# YOTSUBA_GNSS-receiver_MAX_ver_1_4.net
KiCad netlist of a schematic drawn in EAGLE
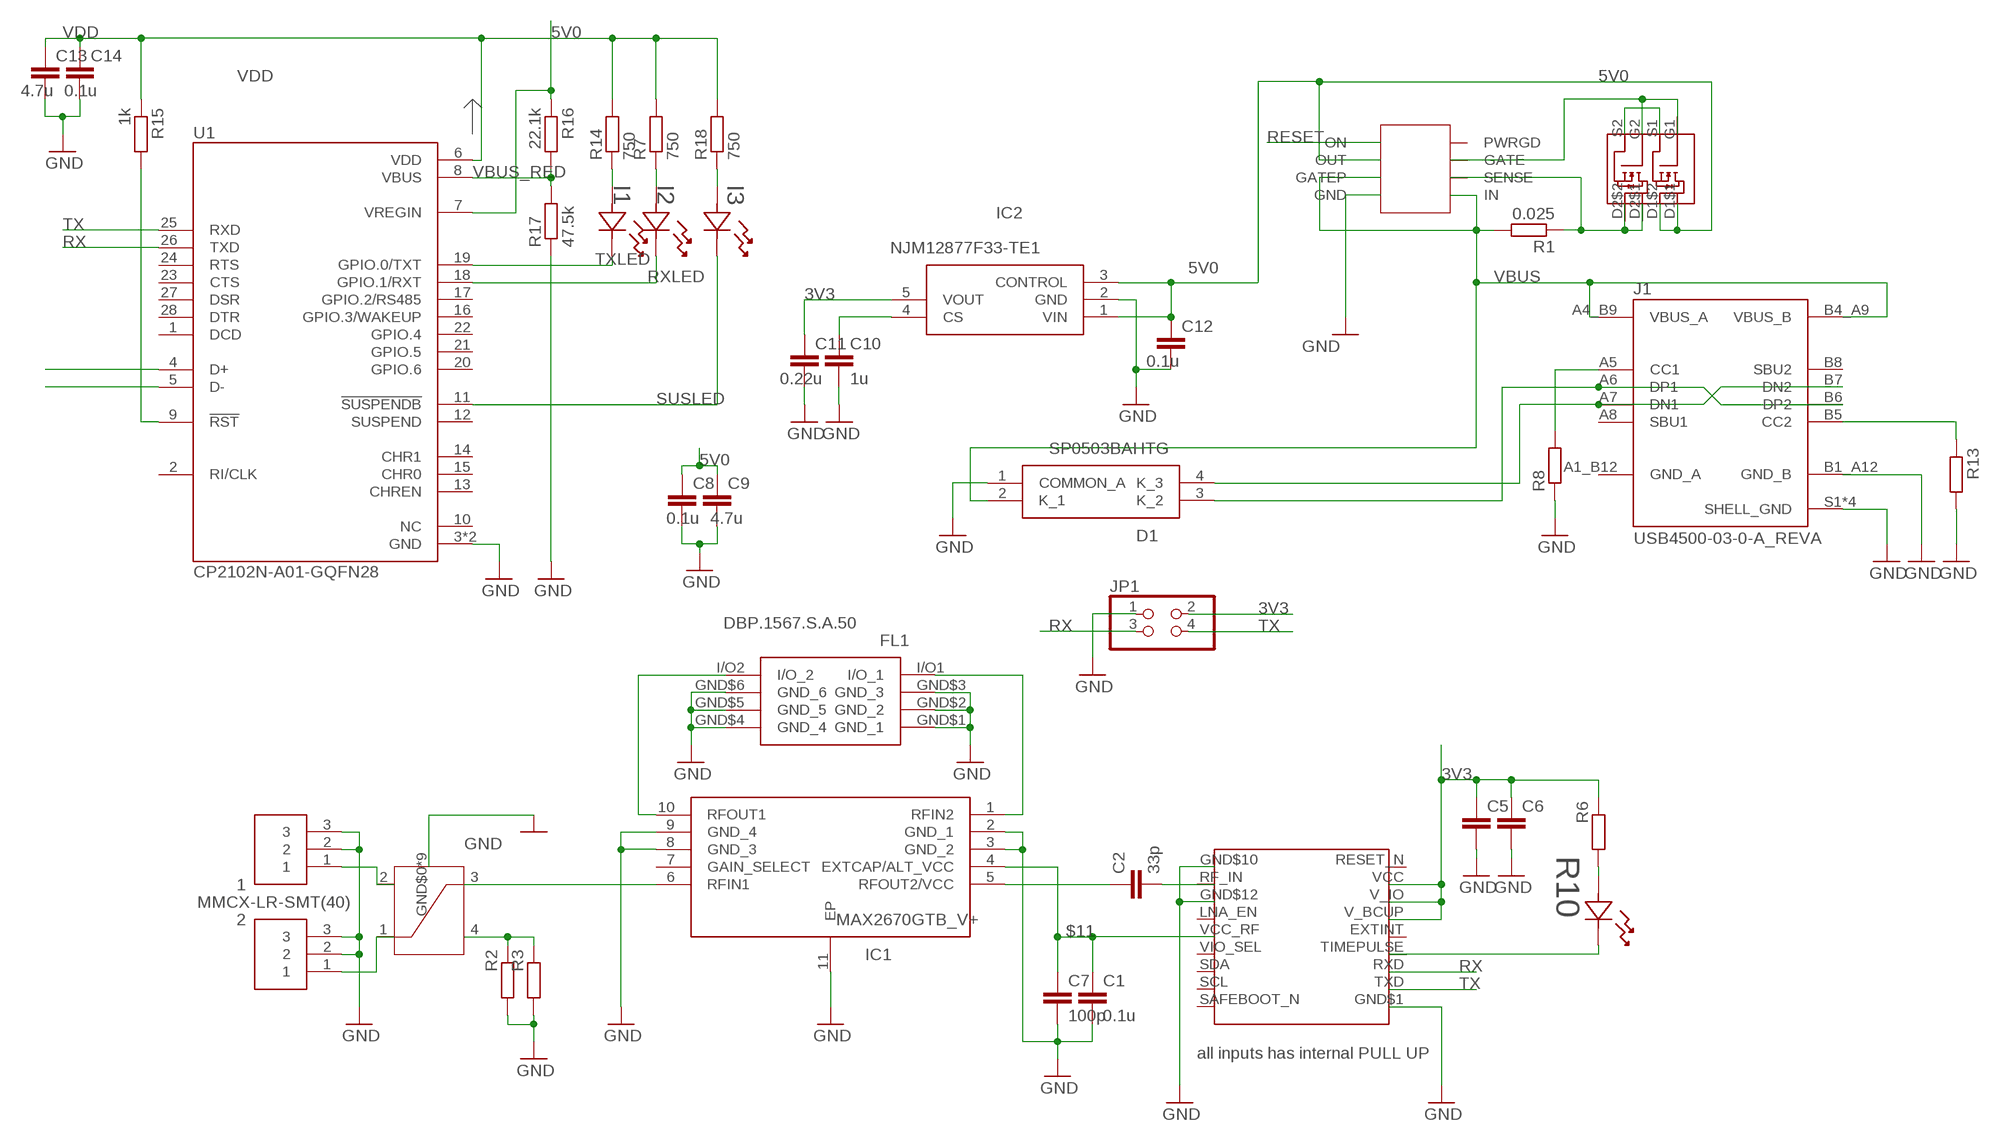
[diagram p0: schematic, sheet 1]

(export (version "E")
  (design (tool "Eeschema 10.0.6"))
  (components
    (comp (ref "1")
      (value "MMCX-LR-SMT(40)")
      (footprint "eagle-import:MMCX-LR-SMT(40)")
      (libsource (lib "eagle-import") (part "MMCX-LR-SMT(40)"))
    )
    (comp (ref "2")
      (value "MMCX-LR-SMT(40)")
      (footprint "eagle-import:MMCX-LR-SMT(40)")
      (libsource (lib "eagle-import") (part "MMCX-LR-SMT(40)"))
    )
    (comp (ref "C1")
      (value "0.1u")
      (footprint "eagle-import:C1608")
      (libsource (lib "eagle-import") (part "C-EUC1608"))
    )
    (comp (ref "C2")
      (value "33p")
      (footprint "eagle-import:C1608")
      (libsource (lib "eagle-import") (part "C-EUC1608"))
    )
    (comp (ref "C5")
      (value "C-EUC1608")
      (footprint "eagle-import:C1608")
      (libsource (lib "eagle-import") (part "C-EUC1608"))
    )
    (comp (ref "C6")
      (value "C-EUC1608")
      (footprint "eagle-import:C1608")
      (libsource (lib "eagle-import") (part "C-EUC1608"))
    )
    (comp (ref "C7")
      (value "100p")
      (footprint "eagle-import:C1608")
      (libsource (lib "eagle-import") (part "C-EUC1608"))
    )
    (comp (ref "C8")
      (value "0.1u")
      (footprint "eagle-import:C1608")
      (libsource (lib "eagle-import") (part "C-EUC1608"))
    )
    (comp (ref "C9")
      (value "4.7u")
      (footprint "eagle-import:C1608")
      (libsource (lib "eagle-import") (part "C-EUC1608"))
    )
    (comp (ref "C10")
      (value "1u")
      (footprint "eagle-import:C1608")
      (libsource (lib "eagle-import") (part "C-EUC1608"))
    )
    (comp (ref "C11")
      (value "0.22u")
      (footprint "eagle-import:C1608")
      (libsource (lib "eagle-import") (part "C-EUC1608"))
    )
    (comp (ref "C12")
      (value "0.1u")
      (footprint "eagle-import:C1608")
      (libsource (lib "eagle-import") (part "C-EUC1608"))
    )
    (comp (ref "C13")
      (value "4.7u")
      (footprint "eagle-import:C1608")
      (libsource (lib "eagle-import") (part "C-EUC1608"))
    )
    (comp (ref "C14")
      (value "0.1u")
      (footprint "eagle-import:C1608")
      (libsource (lib "eagle-import") (part "C-EUC1608"))
    )
    (comp (ref "D1")
      (value "SP0503BAHTG")
      (footprint "eagle-import:SP0503BAHTG")
      (fields (field (name "MOUSER_PART_NUMBER") "576-SP0503BAHTG"))
      (libsource (lib "eagle-import") (part "SP0503BAHTG"))
    )
    (comp (ref "FL1")
      (value "DBP.1567.S.A.50")
      (footprint "eagle-import:DBP1567SA50")
      (libsource (lib "eagle-import") (part "DBP.1567.S.A.50"))
    )
    (comp (ref "I1")
      (value "SML-E12P8WT86")
      (footprint "eagle-import:LED_SMLD12_ROM")
      (fields (field (name "COPYRIGHT") "Copyright (C) 2023 Ultra Librarian. All rights reserved."))
      (libsource (lib "eagle-import") (part "SML-E12P8WT86"))
    )
    (comp (ref "I2")
      (value "SML-E12P8WT86")
      (footprint "eagle-import:LED_SMLD12_ROM")
      (fields (field (name "COPYRIGHT") "Copyright (C) 2023 Ultra Librarian. All rights reserved."))
      (libsource (lib "eagle-import") (part "SML-E12P8WT86"))
    )
    (comp (ref "I3")
      (value "SML-E12P8WT86")
      (footprint "eagle-import:LED_SMLD12_ROM")
      (fields (field (name "COPYRIGHT") "Copyright (C) 2023 Ultra Librarian. All rights reserved."))
      (libsource (lib "eagle-import") (part "SML-E12P8WT86"))
    )
    (comp (ref "IC1")
      (value "MAX2670GTB_V+")
      (footprint "eagle-import:SON50P300X300X80-11N")
      (fields
        (field (name "MANUFACTURER_PART_NUMBER") "MAX2670GTB/V+")
        (field (name "MOUSER_PART_NUMBER") "700-MAX2670GTB/V+")
      )
      (libsource (lib "eagle-import") (part "MAX2670GTB_V+"))
    )
    (comp (ref "IC2")
      (value "NJM12877F33-TE1")
      (footprint "eagle-import:SOT95P280X120-5N")
      (fields (field (name "MOUSER_PART_NUMBER") "513-NJM12877F33-TE1"))
      (libsource (lib "eagle-import") (part "NJM12877F33-TE1"))
    )
    (comp (ref "J1")
      (value "USB4500-03-0-A_REVA")
      (footprint "eagle-import:GCT_USB4500-03-0-A_REVA")
      (fields
        (field (name "DIGI-KEY_PART_NUMBER") "2073-USB4500-03-0-ATR-ND")
        (field (name "MF") "Global Connector Technology")
        (field (name "MP") "USB4500-03-0-A")
      )
      (libsource (lib "eagle-import") (part "USB4500-03-0-A_REVA"))
    )
    (comp (ref "JP1")
      (value "PINHD-2X2")
      (footprint "eagle-import:2X02")
      (libsource (lib "eagle-import") (part "PINHD-2X2"))
    )
    (comp (ref "R1")
      (value "0.025")
      (footprint "eagle-import:R0603")
      (libsource (lib "eagle-import") (part "R-EU_R0603"))
    )
    (comp (ref "R2")
      (value "R-EU_R0603")
      (footprint "eagle-import:R0603")
      (libsource (lib "eagle-import") (part "R-EU_R0603"))
    )
    (comp (ref "R3")
      (value "R-EU_R0603")
      (footprint "eagle-import:R0603")
      (libsource (lib "eagle-import") (part "R-EU_R0603"))
    )
    (comp (ref "R6")
      (value "R-EU_R0603")
      (footprint "eagle-import:R0603")
      (libsource (lib "eagle-import") (part "R-EU_R0603"))
    )
    (comp (ref "R7")
      (value "750")
      (footprint "eagle-import:R0603")
      (libsource (lib "eagle-import") (part "R-EU_R0603"))
    )
    (comp (ref "R8")
      (value "R-EU_R0603")
      (footprint "eagle-import:R0603")
      (libsource (lib "eagle-import") (part "R-EU_R0603"))
    )
    (comp (ref "R10")
      (value "SML-E12P8WT86")
      (footprint "eagle-import:LED_SMLD12_ROM")
      (fields (field (name "COPYRIGHT") "Copyright (C) 2023 Ultra Librarian. All rights reserved."))
      (libsource (lib "eagle-import") (part "SML-E12P8WT86"))
    )
    (comp (ref "R13")
      (value "R-EU_R0603")
      (footprint "eagle-import:R0603")
      (libsource (lib "eagle-import") (part "R-EU_R0603"))
    )
    (comp (ref "R14")
      (value "750")
      (footprint "eagle-import:R0603")
      (libsource (lib "eagle-import") (part "R-EU_R0603"))
    )
    (comp (ref "R15")
      (value "1k")
      (footprint "eagle-import:R0603")
      (libsource (lib "eagle-import") (part "R-EU_R0603"))
    )
    (comp (ref "R16")
      (value "22.1k")
      (footprint "eagle-import:R0603")
      (libsource (lib "eagle-import") (part "R-EU_R0603"))
    )
    (comp (ref "R17")
      (value "47.5k")
      (footprint "eagle-import:R0603")
      (libsource (lib "eagle-import") (part "R-EU_R0603"))
    )
    (comp (ref "R18")
      (value "750")
      (footprint "eagle-import:R0603")
      (libsource (lib "eagle-import") (part "R-EU_R0603"))
    )
    (comp (ref "U$1")
      (value "MAX_M10S")
      (footprint "eagle-import:MAX-M10S")
      (libsource (lib "eagle-import") (part "MAX_M10S"))
    )
    (comp (ref "U$3")
      (value "HC125.A")
      (footprint "eagle-import:HC125.A")
      (libsource (lib "eagle-import") (part "HC125.A"))
    )
    (comp (ref "U$7")
      (value "DMG6898LSD")
      (footprint "eagle-import:SOIC127P600X150-8N")
      (libsource (lib "eagle-import") (part "DMG6898LSD"))
    )
    (comp (ref "U$8")
      (value "LTC4361")
      (footprint "eagle-import:SOP65P280X100-8N")
      (libsource (lib "eagle-import") (part "LTC4361"))
    )
    (comp (ref "U1")
      (value "CP2102N-A01-GQFN28")
      (footprint "eagle-import:QFN50P500X500X80-29N")
      (fields (field (name "MF") "Silicon Labs"))
      (libsource (lib "eagle-import") (part "CP2102N-A01-GQFN28"))
    )
  )
  (nets
    (net (code "1") (name "/$11") (class "Default")
      (node (ref "C1") (pin "1") (pinfunction "1_1") (pintype "passive"))
      (node (ref "C7") (pin "1") (pinfunction "1_1") (pintype "passive"))
      (node (ref "IC1") (pin "4") (pinfunction "EXTCAP/ALT_VCC_4") (pintype "bidirectional"))
      (node (ref "U$1") (pin "VCC_RF") (pinfunction "VCC_RF_VCC_RF") (pintype "bidirectional"))
    )
    (net (code "2") (name "/3V3") (class "Default")
      (node (ref "C11") (pin "1") (pinfunction "1_1") (pintype "passive"))
      (node (ref "C5") (pin "1") (pinfunction "1_1") (pintype "passive"))
      (node (ref "C6") (pin "1") (pinfunction "1_1") (pintype "passive"))
      (node (ref "IC2") (pin "5") (pinfunction "VOUT_5") (pintype "bidirectional"))
      (node (ref "JP1") (pin "2") (pinfunction "2_2") (pintype "passive"))
      (node (ref "R6") (pin "2") (pinfunction "2_2") (pintype "passive"))
      (node (ref "U$1") (pin "VCC") (pinfunction "VCC_VCC") (pintype "bidirectional"))
      (node (ref "U$1") (pin "V_BCUP") (pinfunction "V_BCKP_V_BCUP") (pintype "bidirectional"))
      (node (ref "U$1") (pin "V_IO") (pinfunction "V_IO_V_IO") (pintype "bidirectional"))
    )
    (net (code "3") (name "/5V0") (class "Default")
      (node (ref "C12") (pin "1") (pinfunction "1_1") (pintype "passive"))
      (node (ref "C8") (pin "1") (pinfunction "1_1") (pintype "passive"))
      (node (ref "C9") (pin "1") (pinfunction "1_1") (pintype "passive"))
      (node (ref "IC2") (pin "1") (pinfunction "VIN_1") (pintype "bidirectional"))
      (node (ref "IC2") (pin "3") (pinfunction "CONTROL_3") (pintype "bidirectional"))
      (node (ref "R16") (pin "1") (pinfunction "1_1") (pintype "passive"))
      (node (ref "U$7") (pin "D1$1") (pinfunction "D1$1_D1$1") (pintype "bidirectional"))
      (node (ref "U$7") (pin "D1$2") (pinfunction "D1$2_D1$2") (pintype "bidirectional"))
      (node (ref "U$8") (pin "OUT") (pinfunction "OUT_OUT") (pintype "bidirectional"))
      (node (ref "U1") (pin "7") (pinfunction "VREGIN_7") (pintype "power_in"))
    )
    (net (code "4") (name "/D+") (class "Default")
      (node (ref "D1") (pin "3") (pinfunction "K_2_3") (pintype "bidirectional"))
      (node (ref "J1") (pin "A6") (pinfunction "DP1_A6") (pintype "bidirectional"))
      (node (ref "J1") (pin "B6") (pinfunction "DP2_B6") (pintype "bidirectional"))
      (node (ref "U1") (pin "4") (pinfunction "D+_4") (pintype "bidirectional"))
    )
    (net (code "5") (name "/D-") (class "Default")
      (node (ref "D1") (pin "4") (pinfunction "K_3_4") (pintype "bidirectional"))
      (node (ref "J1") (pin "A7") (pinfunction "DN1_A7") (pintype "bidirectional"))
      (node (ref "J1") (pin "B7") (pinfunction "DN2_B7") (pintype "bidirectional"))
      (node (ref "U1") (pin "5") (pinfunction "D-_5") (pintype "bidirectional"))
    )
    (net (code "6") (name "/GND_A") (class "Default")
      (node (ref "J1") (pin "A1_B12") (pinfunction "GND_A_A1_B12") (pintype "power_in"))
    )
    (net (code "7") (name "/RESET") (class "Default")
      (node (ref "U$8") (pin "ON") (pinfunction "ON_ON") (pintype "bidirectional"))
    )
    (net (code "8") (name "/RX") (class "Default")
      (node (ref "JP1") (pin "3") (pinfunction "3_3") (pintype "passive"))
      (node (ref "U$1") (pin "RXD") (pinfunction "RXD_RXD") (pintype "bidirectional"))
      (node (ref "U1") (pin "26") (pinfunction "TXD_26") (pintype "output"))
    )
    (net (code "9") (name "/RXLED") (class "Default")
      (node (ref "I2") (pin "1") (pinfunction "1_1") (pintype "passive"))
      (node (ref "U1") (pin "18") (pinfunction "GPIO.1/RXT_18") (pintype "bidirectional"))
    )
    (net (code "10") (name "/SUSLED") (class "Default")
      (node (ref "I3") (pin "1") (pinfunction "1_1") (pintype "passive"))
      (node (ref "U1") (pin "11") (pinfunction "~{SUSPENDB}_11") (pintype "output"))
    )
    (net (code "11") (name "/TX") (class "Default")
      (node (ref "JP1") (pin "4") (pinfunction "4_4") (pintype "passive"))
      (node (ref "U$1") (pin "TXD") (pinfunction "TXD_TXD") (pintype "bidirectional"))
      (node (ref "U1") (pin "25") (pinfunction "RXD_25") (pintype "input"))
    )
    (net (code "12") (name "/TXLED") (class "Default")
      (node (ref "I1") (pin "1") (pinfunction "1_1") (pintype "passive"))
      (node (ref "U1") (pin "19") (pinfunction "GPIO.0/TXT_19") (pintype "bidirectional"))
    )
    (net (code "13") (name "/VBUS") (class "Default")
      (node (ref "D1") (pin "2") (pinfunction "K_1_2") (pintype "bidirectional"))
      (node (ref "J1") (pin "A4_B9") (pinfunction "VBUS_A_A4_B9") (pintype "power_in"))
      (node (ref "J1") (pin "B4_A9") (pinfunction "VBUS_B_B4_A9") (pintype "power_in"))
      (node (ref "R1") (pin "2") (pinfunction "2_2") (pintype "passive"))
      (node (ref "U$8") (pin "GATEP") (pinfunction "GATEP_GATEP") (pintype "bidirectional"))
      (node (ref "U$8") (pin "IN") (pinfunction "IN_IN") (pintype "bidirectional"))
    )
    (net (code "14") (name "/VBUS_RED") (class "Default")
      (node (ref "R16") (pin "2") (pinfunction "2_2") (pintype "passive"))
      (node (ref "R17") (pin "2") (pinfunction "2_2") (pintype "passive"))
      (node (ref "U1") (pin "8") (pinfunction "VBUS_8") (pintype "power_in"))
    )
    (net (code "15") (name "/VDD") (class "Default")
      (node (ref "C13") (pin "1") (pinfunction "1_1") (pintype "passive"))
      (node (ref "C14") (pin "1") (pinfunction "1_1") (pintype "passive"))
      (node (ref "R14") (pin "2") (pinfunction "2_2") (pintype "passive"))
      (node (ref "R15") (pin "1") (pinfunction "1_1") (pintype "passive"))
      (node (ref "R18") (pin "2") (pinfunction "2_2") (pintype "passive"))
      (node (ref "R7") (pin "2") (pinfunction "2_2") (pintype "passive"))
      (node (ref "U1") (pin "6") (pinfunction "VDD_6") (pintype "power_in"))
    )
    (net (code "16") (name "GND") (class "Default")
      (node (ref "1") (pin "2") (pinfunction "2_2") (pintype "bidirectional"))
      (node (ref "1") (pin "3") (pinfunction "3_3") (pintype "bidirectional"))
      (node (ref "2") (pin "2") (pinfunction "2_2") (pintype "bidirectional"))
      (node (ref "2") (pin "3") (pinfunction "3_3") (pintype "bidirectional"))
      (node (ref "C1") (pin "2") (pinfunction "2_2") (pintype "passive"))
      (node (ref "C10") (pin "2") (pinfunction "2_2") (pintype "passive"))
      (node (ref "C11") (pin "2") (pinfunction "2_2") (pintype "passive"))
      (node (ref "C12") (pin "2") (pinfunction "2_2") (pintype "passive"))
      (node (ref "C13") (pin "2") (pinfunction "2_2") (pintype "passive"))
      (node (ref "C14") (pin "2") (pinfunction "2_2") (pintype "passive"))
      (node (ref "C5") (pin "2") (pinfunction "2_2") (pintype "passive"))
      (node (ref "C6") (pin "2") (pinfunction "2_2") (pintype "passive"))
      (node (ref "C7") (pin "2") (pinfunction "2_2") (pintype "passive"))
      (node (ref "C8") (pin "2") (pinfunction "2_2") (pintype "passive"))
      (node (ref "C9") (pin "2") (pinfunction "2_2") (pintype "passive"))
      (node (ref "D1") (pin "1") (pinfunction "COMMON_A_1") (pintype "bidirectional"))
      (node (ref "FL1") (pin "GND$1") (pinfunction "GND_1_GND$1") (pintype "bidirectional"))
      (node (ref "FL1") (pin "GND$2") (pinfunction "GND_2_GND$2") (pintype "bidirectional"))
      (node (ref "FL1") (pin "GND$3") (pinfunction "GND_3_GND$3") (pintype "bidirectional"))
      (node (ref "FL1") (pin "GND$4") (pinfunction "GND_4_GND$4") (pintype "bidirectional"))
      (node (ref "FL1") (pin "GND$5") (pinfunction "GND_5_GND$5") (pintype "bidirectional"))
      (node (ref "FL1") (pin "GND$6") (pinfunction "GND_6_GND$6") (pintype "bidirectional"))
      (node (ref "IC1") (pin "11") (pinfunction "EP_11") (pintype "bidirectional"))
      (node (ref "IC1") (pin "2") (pinfunction "GND_1_2") (pintype "bidirectional"))
      (node (ref "IC1") (pin "3") (pinfunction "GND_2_3") (pintype "bidirectional"))
      (node (ref "IC1") (pin "8") (pinfunction "GND_3_8") (pintype "bidirectional"))
      (node (ref "IC1") (pin "9") (pinfunction "GND_4_9") (pintype "bidirectional"))
      (node (ref "IC2") (pin "2") (pinfunction "GND_2") (pintype "bidirectional"))
      (node (ref "J1") (pin "B1_A12") (pinfunction "GND_B_B1_A12") (pintype "power_in"))
      (node (ref "J1") (pin "S1") (pinfunction "SHELL_GND_S1") (pintype "power_in"))
      (node (ref "J1") (pin "S2") (pinfunction "SHELL_GND_S2") (pintype "power_in"))
      (node (ref "J1") (pin "S3") (pinfunction "SHELL_GND_S3") (pintype "power_in"))
      (node (ref "J1") (pin "S4") (pinfunction "SHELL_GND_S4") (pintype "power_in"))
      (node (ref "JP1") (pin "1") (pinfunction "1_1") (pintype "passive"))
      (node (ref "R13") (pin "2") (pinfunction "2_2") (pintype "passive"))
      (node (ref "R17") (pin "1") (pinfunction "1_1") (pintype "passive"))
      (node (ref "R2") (pin "1") (pinfunction "1_1") (pintype "passive"))
      (node (ref "R3") (pin "1") (pinfunction "1_1") (pintype "passive"))
      (node (ref "R8") (pin "1") (pinfunction "1_1") (pintype "passive"))
      (node (ref "U$1") (pin "GND$1") (pinfunction "GND$1_GND$1") (pintype "bidirectional"))
      (node (ref "U$1") (pin "GND$10") (pinfunction "GND$10_GND$10") (pintype "bidirectional"))
      (node (ref "U$1") (pin "GND$12") (pinfunction "GND$12_GND$12") (pintype "bidirectional"))
      (node (ref "U$3") (pin "GND$0") (pinfunction "GND_GND$0") (pintype "bidirectional"))
      (node (ref "U$3") (pin "GND$1") (pinfunction "GND_GND$1") (pintype "bidirectional"))
      (node (ref "U$3") (pin "GND$2") (pinfunction "GND_GND$2") (pintype "bidirectional"))
      (node (ref "U$3") (pin "GND$3") (pinfunction "GND_GND$3") (pintype "bidirectional"))
      (node (ref "U$3") (pin "GND$4") (pinfunction "GND_GND$4") (pintype "bidirectional"))
      (node (ref "U$3") (pin "GND$5") (pinfunction "GND_GND$5") (pintype "bidirectional"))
      (node (ref "U$3") (pin "GND$6") (pinfunction "GND_GND$6") (pintype "bidirectional"))
      (node (ref "U$3") (pin "GND$7") (pinfunction "GND_GND$7") (pintype "bidirectional"))
      (node (ref "U$3") (pin "GND$8") (pinfunction "GND_GND$8") (pintype "bidirectional"))
      (node (ref "U$8") (pin "GND") (pinfunction "GND_GND") (pintype "bidirectional"))
      (node (ref "U1") (pin "29") (pinfunction "GND_29") (pintype "power_in"))
      (node (ref "U1") (pin "3") (pinfunction "GND_3") (pintype "power_in"))
    )
    (net (code "17") (name "Net-(1-Pad1)") (class "Default")
      (node (ref "1") (pin "1") (pinfunction "1_1") (pintype "bidirectional"))
      (node (ref "U$3") (pin "2") (pinfunction "2_2") (pintype "bidirectional"))
    )
    (net (code "18") (name "Net-(2-Pad1)") (class "Default")
      (node (ref "2") (pin "1") (pinfunction "1_1") (pintype "bidirectional"))
      (node (ref "U$3") (pin "1") (pinfunction "1_1") (pintype "bidirectional"))
    )
    (net (code "19") (name "Net-(C2-Pad2)") (class "Default")
      (node (ref "C2") (pin "2") (pinfunction "2_2") (pintype "passive"))
      (node (ref "U$1") (pin "RF_IN") (pinfunction "RF_IN_RF_IN") (pintype "bidirectional"))
    )
    (net (code "20") (name "Net-(FL1-I{slash}O_1)") (class "Default")
      (node (ref "FL1") (pin "I/O1") (pinfunction "I/O_1_I/O1") (pintype "bidirectional"))
      (node (ref "IC1") (pin "1") (pinfunction "RFIN2_1") (pintype "bidirectional"))
    )
    (net (code "21") (name "Net-(FL1-I{slash}O_2)") (class "Default")
      (node (ref "FL1") (pin "I/O2") (pinfunction "I/O_2_I/O2") (pintype "bidirectional"))
      (node (ref "IC1") (pin "10") (pinfunction "RFOUT1_10") (pintype "bidirectional"))
    )
    (net (code "22") (name "Net-(I1-Pad2)") (class "Default")
      (node (ref "I1") (pin "2") (pinfunction "2_2") (pintype "passive"))
      (node (ref "R14") (pin "1") (pinfunction "1_1") (pintype "passive"))
    )
    (net (code "23") (name "Net-(I2-Pad2)") (class "Default")
      (node (ref "I2") (pin "2") (pinfunction "2_2") (pintype "passive"))
      (node (ref "R7") (pin "1") (pinfunction "1_1") (pintype "passive"))
    )
    (net (code "24") (name "Net-(I3-Pad2)") (class "Default")
      (node (ref "I3") (pin "2") (pinfunction "2_2") (pintype "passive"))
      (node (ref "R18") (pin "1") (pinfunction "1_1") (pintype "passive"))
    )
    (net (code "25") (name "Net-(IC1-RFIN1)") (class "Default")
      (node (ref "IC1") (pin "6") (pinfunction "RFIN1_6") (pintype "bidirectional"))
      (node (ref "U$3") (pin "3") (pinfunction "3_3") (pintype "bidirectional"))
    )
    (net (code "26") (name "Net-(IC1-RFOUT2{slash}VCC)") (class "Default")
      (node (ref "C2") (pin "1") (pinfunction "1_1") (pintype "passive"))
      (node (ref "IC1") (pin "5") (pinfunction "RFOUT2/VCC_5") (pintype "bidirectional"))
    )
    (net (code "27") (name "Net-(IC2-CS)") (class "Default")
      (node (ref "C10") (pin "1") (pinfunction "1_1") (pintype "passive"))
      (node (ref "IC2") (pin "4") (pinfunction "CS_4") (pintype "bidirectional"))
    )
    (net (code "28") (name "Net-(J1-CC1)") (class "Default")
      (node (ref "J1") (pin "A5") (pinfunction "CC1_A5") (pintype "bidirectional"))
      (node (ref "R8") (pin "2") (pinfunction "2_2") (pintype "passive"))
    )
    (net (code "29") (name "Net-(J1-CC2)") (class "Default")
      (node (ref "J1") (pin "B5") (pinfunction "CC2_B5") (pintype "bidirectional"))
      (node (ref "R13") (pin "1") (pinfunction "1_1") (pintype "passive"))
    )
    (net (code "30") (name "Net-(R1-Pad1)") (class "Default")
      (node (ref "R1") (pin "1") (pinfunction "1_1") (pintype "passive"))
      (node (ref "U$7") (pin "D2$1") (pinfunction "D2$1_D2$1") (pintype "bidirectional"))
      (node (ref "U$7") (pin "D2$2") (pinfunction "D2$2_D2$2") (pintype "bidirectional"))
      (node (ref "U$8") (pin "SENSE") (pinfunction "SENSE_SENSE") (pintype "bidirectional"))
    )
    (net (code "31") (name "Net-(R2-Pad2)") (class "Default")
      (node (ref "R2") (pin "2") (pinfunction "2_2") (pintype "passive"))
      (node (ref "R3") (pin "2") (pinfunction "2_2") (pintype "passive"))
      (node (ref "U$3") (pin "4") (pinfunction "4_4") (pintype "bidirectional"))
    )
    (net (code "32") (name "Net-(R10-Pad1)") (class "Default")
      (node (ref "R10") (pin "1") (pinfunction "1_1") (pintype "passive"))
      (node (ref "U$1") (pin "TIMEPULSE") (pinfunction "TIMEPULSE_TIMEPULSE") (pintype "bidirectional"))
    )
    (net (code "33") (name "Net-(R10-Pad2)") (class "Default")
      (node (ref "R10") (pin "2") (pinfunction "2_2") (pintype "passive"))
      (node (ref "R6") (pin "1") (pinfunction "1_1") (pintype "passive"))
    )
    (net (code "34") (name "Net-(U$7-PadG1)") (class "Default")
      (node (ref "U$7") (pin "G1") (pinfunction "G1_G1") (pintype "bidirectional"))
      (node (ref "U$7") (pin "G2") (pinfunction "G2_G2") (pintype "bidirectional"))
      (node (ref "U$8") (pin "GATE") (pinfunction "GATE_GATE") (pintype "bidirectional"))
    )
    (net (code "35") (name "Net-(U$7-PadS1)") (class "Default")
      (node (ref "U$7") (pin "S1") (pinfunction "S1_S1") (pintype "bidirectional"))
      (node (ref "U$7") (pin "S2") (pinfunction "S2_S2") (pintype "bidirectional"))
    )
    (net (code "36") (name "Net-(U1-~{RST})") (class "Default")
      (node (ref "R15") (pin "2") (pinfunction "2_2") (pintype "passive"))
      (node (ref "U1") (pin "9") (pinfunction "~{RST}_9") (pintype "input"))
    )
    (net (code "37") (name "unconnected-(IC1-GAIN_SELECT-Pad7)") (class "Default")
      (node (ref "IC1") (pin "7") (pinfunction "GAIN_SELECT_7") (pintype "bidirectional"))
    )
    (net (code "38") (name "unconnected-(J1-SBU1-PadA8)") (class "Default")
      (node (ref "J1") (pin "A8") (pinfunction "SBU1_A8") (pintype "bidirectional"))
    )
    (net (code "39") (name "unconnected-(J1-SBU2-PadB8)") (class "Default")
      (node (ref "J1") (pin "B8") (pinfunction "SBU2_B8") (pintype "bidirectional"))
    )
    (net (code "40") (name "unconnected-(U$1-PadEXTINT)") (class "Default")
      (node (ref "U$1") (pin "EXTINT") (pinfunction "EXTINT_EXTINT") (pintype "bidirectional"))
    )
    (net (code "41") (name "unconnected-(U$1-PadLNA_EN)") (class "Default")
      (node (ref "U$1") (pin "LNA_EN") (pinfunction "LNA_EN_LNA_EN") (pintype "bidirectional"))
    )
    (net (code "42") (name "unconnected-(U$1-PadRESET_N)") (class "Default")
      (node (ref "U$1") (pin "RESET_N") (pinfunction "RESET_N_RESET_N") (pintype "bidirectional"))
    )
    (net (code "43") (name "unconnected-(U$1-PadSAFEBOOT_N)") (class "Default")
      (node (ref "U$1") (pin "SAFEBOOT_N") (pinfunction "SAFEBOOT_N_SAFEBOOT_N") (pintype "bidirectional"))
    )
    (net (code "44") (name "unconnected-(U$1-PadSCL)") (class "Default")
      (node (ref "U$1") (pin "SCL") (pinfunction "SCL_SCL") (pintype "bidirectional"))
    )
    (net (code "45") (name "unconnected-(U$1-PadSDA)") (class "Default")
      (node (ref "U$1") (pin "SDA") (pinfunction "SDA_SDA") (pintype "bidirectional"))
    )
    (net (code "46") (name "unconnected-(U$1-PadVIO_SEL)") (class "Default")
      (node (ref "U$1") (pin "VIO_SEL") (pinfunction "VIO_SEL_VIO_SEL") (pintype "bidirectional"))
    )
    (net (code "47") (name "unconnected-(U$8-PadPWRGD)") (class "Default")
      (node (ref "U$8") (pin "PWRGD") (pinfunction "PWRGD_PWRGD") (pintype "bidirectional"))
    )
    (net (code "48") (name "unconnected-(U1-CHR0-Pad15)") (class "Default")
      (node (ref "U1") (pin "15") (pinfunction "CHR0_15") (pintype "output"))
    )
    (net (code "49") (name "unconnected-(U1-CHR1-Pad14)") (class "Default")
      (node (ref "U1") (pin "14") (pinfunction "CHR1_14") (pintype "output"))
    )
    (net (code "50") (name "unconnected-(U1-CHREN-Pad13)") (class "Default")
      (node (ref "U1") (pin "13") (pinfunction "CHREN_13") (pintype "output"))
    )
    (net (code "51") (name "unconnected-(U1-CTS-Pad23)") (class "Default")
      (node (ref "U1") (pin "23") (pinfunction "CTS_23") (pintype "input"))
    )
    (net (code "52") (name "unconnected-(U1-DCD-Pad1)") (class "Default")
      (node (ref "U1") (pin "1") (pinfunction "DCD_1") (pintype "input"))
    )
    (net (code "53") (name "unconnected-(U1-DSR-Pad27)") (class "Default")
      (node (ref "U1") (pin "27") (pinfunction "DSR_27") (pintype "input"))
    )
    (net (code "54") (name "unconnected-(U1-DTR-Pad28)") (class "Default")
      (node (ref "U1") (pin "28") (pinfunction "DTR_28") (pintype "output"))
    )
    (net (code "55") (name "unconnected-(U1-GPIO.2{slash}RS485-Pad17)") (class "Default")
      (node (ref "U1") (pin "17") (pinfunction "GPIO.2/RS485_17") (pintype "bidirectional"))
    )
    (net (code "56") (name "unconnected-(U1-GPIO.3{slash}WAKEUP-Pad16)") (class "Default")
      (node (ref "U1") (pin "16") (pinfunction "GPIO.3/WAKEUP_16") (pintype "bidirectional"))
    )
    (net (code "57") (name "unconnected-(U1-GPIO.4-Pad22)") (class "Default")
      (node (ref "U1") (pin "22") (pinfunction "GPIO.4_22") (pintype "bidirectional"))
    )
    (net (code "58") (name "unconnected-(U1-GPIO.5-Pad21)") (class "Default")
      (node (ref "U1") (pin "21") (pinfunction "GPIO.5_21") (pintype "bidirectional"))
    )
    (net (code "59") (name "unconnected-(U1-GPIO.6-Pad20)") (class "Default")
      (node (ref "U1") (pin "20") (pinfunction "GPIO.6_20") (pintype "bidirectional"))
    )
    (net (code "60") (name "unconnected-(U1-NC-Pad10)") (class "Default")
      (node (ref "U1") (pin "10") (pinfunction "NC_10") (pintype "no_connect"))
    )
    (net (code "61") (name "unconnected-(U1-RI{slash}CLK-Pad2)") (class "Default")
      (node (ref "U1") (pin "2") (pinfunction "RI/CLK_2") (pintype "bidirectional"))
    )
    (net (code "62") (name "unconnected-(U1-RTS-Pad24)") (class "Default")
      (node (ref "U1") (pin "24") (pinfunction "RTS_24") (pintype "output"))
    )
    (net (code "63") (name "unconnected-(U1-SUSPEND-Pad12)") (class "Default")
      (node (ref "U1") (pin "12") (pinfunction "SUSPEND_12") (pintype "output"))
    )
  )
)
